# ledunit.net
KiCad netlist of a schematic drawn in EAGLE
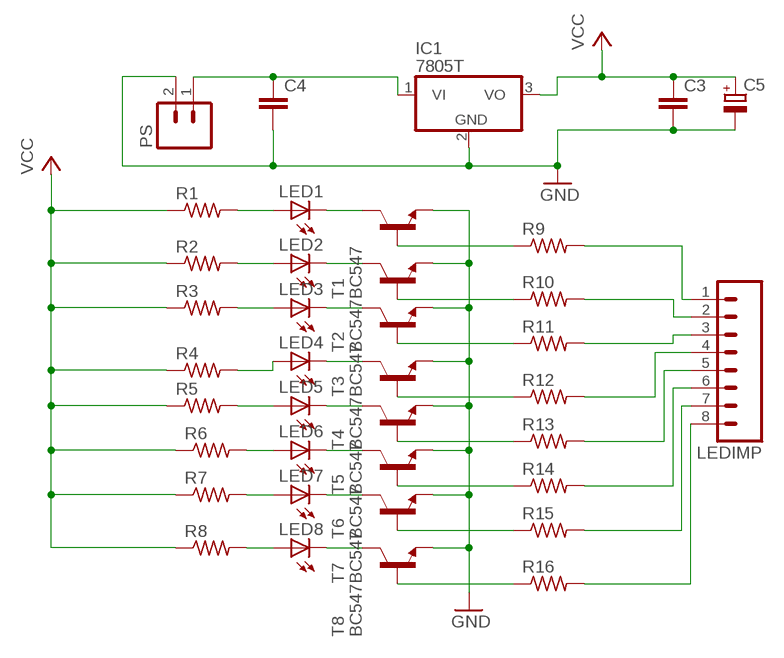
[diagram p0: schematic, sheet 1]

(export (version "E")
  (design (tool "Eeschema 10.0.6"))
  (components
    (comp (ref "C3")
      (value "C-EU025-024X044")
      (footprint "eagle-import:C025-024X044")
      (libsource (lib "eagle-import") (part "C-EU025-024X044"))
    )
    (comp (ref "C4")
      (value "C-EU025-024X044")
      (footprint "eagle-import:C025-024X044")
      (libsource (lib "eagle-import") (part "C-EU025-024X044"))
    )
    (comp (ref "C5")
      (value "CPOL-EUE2,5-6E")
      (footprint "eagle-import:E2,5-6E")
      (libsource (lib "eagle-import") (part "CPOL-EUE2,5-6E"))
    )
    (comp (ref "IC1")
      (value "7805T")
      (footprint "eagle-import:TO220H")
      (libsource (lib "eagle-import") (part "78T05"))
    )
    (comp (ref "LED1")
      (value "LED5MM")
      (footprint "eagle-import:LED5MM")
      (libsource (lib "eagle-import") (part "LED5MM"))
    )
    (comp (ref "LED2")
      (value "LED5MM")
      (footprint "eagle-import:LED5MM")
      (libsource (lib "eagle-import") (part "LED5MM"))
    )
    (comp (ref "LED3")
      (value "LED5MM")
      (footprint "eagle-import:LED5MM")
      (libsource (lib "eagle-import") (part "LED5MM"))
    )
    (comp (ref "LED4")
      (value "LED5MM")
      (footprint "eagle-import:LED5MM")
      (libsource (lib "eagle-import") (part "LED5MM"))
    )
    (comp (ref "LED5")
      (value "LED5MM")
      (footprint "eagle-import:LED5MM")
      (libsource (lib "eagle-import") (part "LED5MM"))
    )
    (comp (ref "LED6")
      (value "LED5MM")
      (footprint "eagle-import:LED5MM")
      (libsource (lib "eagle-import") (part "LED5MM"))
    )
    (comp (ref "LED7")
      (value "LED5MM")
      (footprint "eagle-import:LED5MM")
      (libsource (lib "eagle-import") (part "LED5MM"))
    )
    (comp (ref "LED8")
      (value "LED5MM")
      (footprint "eagle-import:LED5MM")
      (libsource (lib "eagle-import") (part "LED5MM"))
    )
    (comp (ref "LEDIMP")
      (value "M08")
      (footprint "eagle-import:08P")
      (libsource (lib "eagle-import") (part "M08"))
    )
    (comp (ref "PS")
      (value "M02")
      (footprint "eagle-import:02P")
      (libsource (lib "eagle-import") (part "M02"))
    )
    (comp (ref "R1")
      (value "R-US_0204/7")
      (footprint "eagle-import:0204_7")
      (libsource (lib "eagle-import") (part "R-US_0204/7"))
    )
    (comp (ref "R2")
      (value "R-US_0204/7")
      (footprint "eagle-import:0204_7")
      (libsource (lib "eagle-import") (part "R-US_0204/7"))
    )
    (comp (ref "R3")
      (value "R-US_0204/7")
      (footprint "eagle-import:0204_7")
      (libsource (lib "eagle-import") (part "R-US_0204/7"))
    )
    (comp (ref "R4")
      (value "R-US_0204/7")
      (footprint "eagle-import:0204_7")
      (libsource (lib "eagle-import") (part "R-US_0204/7"))
    )
    (comp (ref "R5")
      (value "R-US_0204/7")
      (footprint "eagle-import:0204_7")
      (libsource (lib "eagle-import") (part "R-US_0204/7"))
    )
    (comp (ref "R6")
      (value "R-US_0204/7")
      (footprint "eagle-import:0204_7")
      (libsource (lib "eagle-import") (part "R-US_0204/7"))
    )
    (comp (ref "R7")
      (value "R-US_0204/7")
      (footprint "eagle-import:0204_7")
      (libsource (lib "eagle-import") (part "R-US_0204/7"))
    )
    (comp (ref "R8")
      (value "R-US_0204/7")
      (footprint "eagle-import:0204_7")
      (libsource (lib "eagle-import") (part "R-US_0204/7"))
    )
    (comp (ref "R9")
      (value "R-US_0204/7")
      (footprint "eagle-import:0204_7")
      (libsource (lib "eagle-import") (part "R-US_0204/7"))
    )
    (comp (ref "R10")
      (value "R-US_0204/7")
      (footprint "eagle-import:0204_7")
      (libsource (lib "eagle-import") (part "R-US_0204/7"))
    )
    (comp (ref "R11")
      (value "R-US_0204/7")
      (footprint "eagle-import:0204_7")
      (libsource (lib "eagle-import") (part "R-US_0204/7"))
    )
    (comp (ref "R12")
      (value "R-US_0204/7")
      (footprint "eagle-import:0204_7")
      (libsource (lib "eagle-import") (part "R-US_0204/7"))
    )
    (comp (ref "R13")
      (value "R-US_0204/7")
      (footprint "eagle-import:0204_7")
      (libsource (lib "eagle-import") (part "R-US_0204/7"))
    )
    (comp (ref "R14")
      (value "R-US_0204/7")
      (footprint "eagle-import:0204_7")
      (libsource (lib "eagle-import") (part "R-US_0204/7"))
    )
    (comp (ref "R15")
      (value "R-US_0204/7")
      (footprint "eagle-import:0204_7")
      (libsource (lib "eagle-import") (part "R-US_0204/7"))
    )
    (comp (ref "R16")
      (value "R-US_0204/7")
      (footprint "eagle-import:0204_7")
      (libsource (lib "eagle-import") (part "R-US_0204/7"))
    )
    (comp (ref "T1")
      (value "BC547")
      (footprint "eagle-import:TO92")
      (libsource (lib "eagle-import") (part "BC547"))
    )
    (comp (ref "T2")
      (value "BC547")
      (footprint "eagle-import:TO92")
      (libsource (lib "eagle-import") (part "BC547"))
    )
    (comp (ref "T3")
      (value "BC547")
      (footprint "eagle-import:TO92")
      (libsource (lib "eagle-import") (part "BC547"))
    )
    (comp (ref "T4")
      (value "BC547")
      (footprint "eagle-import:TO92")
      (libsource (lib "eagle-import") (part "BC547"))
    )
    (comp (ref "T5")
      (value "BC547")
      (footprint "eagle-import:TO92")
      (libsource (lib "eagle-import") (part "BC547"))
    )
    (comp (ref "T6")
      (value "BC547")
      (footprint "eagle-import:TO92")
      (libsource (lib "eagle-import") (part "BC547"))
    )
    (comp (ref "T7")
      (value "BC547")
      (footprint "eagle-import:TO92")
      (libsource (lib "eagle-import") (part "BC547"))
    )
    (comp (ref "T8")
      (value "BC547")
      (footprint "eagle-import:TO92")
      (libsource (lib "eagle-import") (part "BC547"))
    )
  )
  (nets
    (net (code "1") (name "GND") (class "Default")
      (node (ref "C3") (pin "2") (pinfunction "2_2") (pintype "passive"))
      (node (ref "C4") (pin "2") (pinfunction "2_2") (pintype "passive"))
      (node (ref "C5") (pin "-") (pinfunction "-_-") (pintype "passive"))
      (node (ref "IC1") (pin "2") (pinfunction "GND_2") (pintype "passive"))
      (node (ref "PS") (pin "2") (pinfunction "2_2") (pintype "passive"))
      (node (ref "T1") (pin "1") (pinfunction "E_1") (pintype "passive"))
      (node (ref "T2") (pin "1") (pinfunction "E_1") (pintype "passive"))
      (node (ref "T3") (pin "1") (pinfunction "E_1") (pintype "passive"))
      (node (ref "T4") (pin "1") (pinfunction "E_1") (pintype "passive"))
      (node (ref "T5") (pin "1") (pinfunction "E_1") (pintype "passive"))
      (node (ref "T6") (pin "1") (pinfunction "E_1") (pintype "passive"))
      (node (ref "T7") (pin "1") (pinfunction "E_1") (pintype "passive"))
      (node (ref "T8") (pin "1") (pinfunction "E_1") (pintype "passive"))
    )
    (net (code "2") (name "Net-(IC1-VI)") (class "Default")
      (node (ref "C4") (pin "1") (pinfunction "1_1") (pintype "passive"))
      (node (ref "IC1") (pin "1") (pinfunction "VI_1") (pintype "input"))
      (node (ref "PS") (pin "1") (pinfunction "1_1") (pintype "passive"))
    )
    (net (code "3") (name "Net-(LED1-C)") (class "Default")
      (node (ref "LED1") (pin "K") (pinfunction "C_K") (pintype "passive"))
      (node (ref "T1") (pin "3") (pinfunction "C_3") (pintype "passive"))
    )
    (net (code "4") (name "Net-(LED1-PadA)") (class "Default")
      (node (ref "LED1") (pin "A") (pinfunction "A_A") (pintype "passive"))
      (node (ref "R1") (pin "2") (pinfunction "2_2") (pintype "passive"))
    )
    (net (code "5") (name "Net-(LED2-C)") (class "Default")
      (node (ref "LED2") (pin "K") (pinfunction "C_K") (pintype "passive"))
      (node (ref "T2") (pin "3") (pinfunction "C_3") (pintype "passive"))
    )
    (net (code "6") (name "Net-(LED2-PadA)") (class "Default")
      (node (ref "LED2") (pin "A") (pinfunction "A_A") (pintype "passive"))
      (node (ref "R2") (pin "2") (pinfunction "2_2") (pintype "passive"))
    )
    (net (code "7") (name "Net-(LED3-C)") (class "Default")
      (node (ref "LED3") (pin "K") (pinfunction "C_K") (pintype "passive"))
      (node (ref "T3") (pin "3") (pinfunction "C_3") (pintype "passive"))
    )
    (net (code "8") (name "Net-(LED3-PadA)") (class "Default")
      (node (ref "LED3") (pin "A") (pinfunction "A_A") (pintype "passive"))
      (node (ref "R3") (pin "2") (pinfunction "2_2") (pintype "passive"))
    )
    (net (code "9") (name "Net-(LED4-C)") (class "Default")
      (node (ref "LED4") (pin "K") (pinfunction "C_K") (pintype "passive"))
      (node (ref "T4") (pin "3") (pinfunction "C_3") (pintype "passive"))
    )
    (net (code "10") (name "Net-(LED4-PadA)") (class "Default")
      (node (ref "LED4") (pin "A") (pinfunction "A_A") (pintype "passive"))
      (node (ref "R4") (pin "2") (pinfunction "2_2") (pintype "passive"))
    )
    (net (code "11") (name "Net-(LED5-C)") (class "Default")
      (node (ref "LED5") (pin "K") (pinfunction "C_K") (pintype "passive"))
      (node (ref "T5") (pin "3") (pinfunction "C_3") (pintype "passive"))
    )
    (net (code "12") (name "Net-(LED5-PadA)") (class "Default")
      (node (ref "LED5") (pin "A") (pinfunction "A_A") (pintype "passive"))
      (node (ref "R5") (pin "2") (pinfunction "2_2") (pintype "passive"))
    )
    (net (code "13") (name "Net-(LED6-C)") (class "Default")
      (node (ref "LED6") (pin "K") (pinfunction "C_K") (pintype "passive"))
      (node (ref "T6") (pin "3") (pinfunction "C_3") (pintype "passive"))
    )
    (net (code "14") (name "Net-(LED6-PadA)") (class "Default")
      (node (ref "LED6") (pin "A") (pinfunction "A_A") (pintype "passive"))
      (node (ref "R6") (pin "2") (pinfunction "2_2") (pintype "passive"))
    )
    (net (code "15") (name "Net-(LED7-C)") (class "Default")
      (node (ref "LED7") (pin "K") (pinfunction "C_K") (pintype "passive"))
      (node (ref "T7") (pin "3") (pinfunction "C_3") (pintype "passive"))
    )
    (net (code "16") (name "Net-(LED7-PadA)") (class "Default")
      (node (ref "LED7") (pin "A") (pinfunction "A_A") (pintype "passive"))
      (node (ref "R7") (pin "2") (pinfunction "2_2") (pintype "passive"))
    )
    (net (code "17") (name "Net-(LED8-C)") (class "Default")
      (node (ref "LED8") (pin "K") (pinfunction "C_K") (pintype "passive"))
      (node (ref "T8") (pin "3") (pinfunction "C_3") (pintype "passive"))
    )
    (net (code "18") (name "Net-(LED8-PadA)") (class "Default")
      (node (ref "LED8") (pin "A") (pinfunction "A_A") (pintype "passive"))
      (node (ref "R8") (pin "2") (pinfunction "2_2") (pintype "passive"))
    )
    (net (code "19") (name "Net-(LEDIMP-Pad1)") (class "Default")
      (node (ref "LEDIMP") (pin "1") (pinfunction "1_1") (pintype "passive"))
      (node (ref "R9") (pin "2") (pinfunction "2_2") (pintype "passive"))
    )
    (net (code "20") (name "Net-(LEDIMP-Pad2)") (class "Default")
      (node (ref "LEDIMP") (pin "2") (pinfunction "2_2") (pintype "passive"))
      (node (ref "R10") (pin "2") (pinfunction "2_2") (pintype "passive"))
    )
    (net (code "21") (name "Net-(LEDIMP-Pad3)") (class "Default")
      (node (ref "LEDIMP") (pin "3") (pinfunction "3_3") (pintype "passive"))
      (node (ref "R11") (pin "2") (pinfunction "2_2") (pintype "passive"))
    )
    (net (code "22") (name "Net-(LEDIMP-Pad4)") (class "Default")
      (node (ref "LEDIMP") (pin "4") (pinfunction "4_4") (pintype "passive"))
      (node (ref "R12") (pin "2") (pinfunction "2_2") (pintype "passive"))
    )
    (net (code "23") (name "Net-(LEDIMP-Pad5)") (class "Default")
      (node (ref "LEDIMP") (pin "5") (pinfunction "5_5") (pintype "passive"))
      (node (ref "R13") (pin "2") (pinfunction "2_2") (pintype "passive"))
    )
    (net (code "24") (name "Net-(LEDIMP-Pad6)") (class "Default")
      (node (ref "LEDIMP") (pin "6") (pinfunction "6_6") (pintype "passive"))
      (node (ref "R14") (pin "2") (pinfunction "2_2") (pintype "passive"))
    )
    (net (code "25") (name "Net-(LEDIMP-Pad7)") (class "Default")
      (node (ref "LEDIMP") (pin "7") (pinfunction "7_7") (pintype "passive"))
      (node (ref "R15") (pin "2") (pinfunction "2_2") (pintype "passive"))
    )
    (net (code "26") (name "Net-(LEDIMP-Pad8)") (class "Default")
      (node (ref "LEDIMP") (pin "8") (pinfunction "8_8") (pintype "passive"))
      (node (ref "R16") (pin "2") (pinfunction "2_2") (pintype "passive"))
    )
    (net (code "27") (name "Net-(T1-B)") (class "Default")
      (node (ref "R9") (pin "1") (pinfunction "1_1") (pintype "passive"))
      (node (ref "T1") (pin "2") (pinfunction "B_2") (pintype "passive"))
    )
    (net (code "28") (name "Net-(T2-B)") (class "Default")
      (node (ref "R10") (pin "1") (pinfunction "1_1") (pintype "passive"))
      (node (ref "T2") (pin "2") (pinfunction "B_2") (pintype "passive"))
    )
    (net (code "29") (name "Net-(T3-B)") (class "Default")
      (node (ref "R11") (pin "1") (pinfunction "1_1") (pintype "passive"))
      (node (ref "T3") (pin "2") (pinfunction "B_2") (pintype "passive"))
    )
    (net (code "30") (name "Net-(T4-B)") (class "Default")
      (node (ref "R12") (pin "1") (pinfunction "1_1") (pintype "passive"))
      (node (ref "T4") (pin "2") (pinfunction "B_2") (pintype "passive"))
    )
    (net (code "31") (name "Net-(T5-B)") (class "Default")
      (node (ref "R13") (pin "1") (pinfunction "1_1") (pintype "passive"))
      (node (ref "T5") (pin "2") (pinfunction "B_2") (pintype "passive"))
    )
    (net (code "32") (name "Net-(T6-B)") (class "Default")
      (node (ref "R14") (pin "1") (pinfunction "1_1") (pintype "passive"))
      (node (ref "T6") (pin "2") (pinfunction "B_2") (pintype "passive"))
    )
    (net (code "33") (name "Net-(T7-B)") (class "Default")
      (node (ref "R15") (pin "1") (pinfunction "1_1") (pintype "passive"))
      (node (ref "T7") (pin "2") (pinfunction "B_2") (pintype "passive"))
    )
    (net (code "34") (name "Net-(T8-B)") (class "Default")
      (node (ref "R16") (pin "1") (pinfunction "1_1") (pintype "passive"))
      (node (ref "T8") (pin "2") (pinfunction "B_2") (pintype "passive"))
    )
    (net (code "35") (name "VCC") (class "Default")
      (node (ref "C3") (pin "1") (pinfunction "1_1") (pintype "passive"))
      (node (ref "C5") (pin "+") (pinfunction "+_+") (pintype "passive"))
      (node (ref "IC1") (pin "3") (pinfunction "VO_3") (pintype "passive"))
      (node (ref "R1") (pin "1") (pinfunction "1_1") (pintype "passive"))
      (node (ref "R2") (pin "1") (pinfunction "1_1") (pintype "passive"))
      (node (ref "R3") (pin "1") (pinfunction "1_1") (pintype "passive"))
      (node (ref "R4") (pin "1") (pinfunction "1_1") (pintype "passive"))
      (node (ref "R5") (pin "1") (pinfunction "1_1") (pintype "passive"))
      (node (ref "R6") (pin "1") (pinfunction "1_1") (pintype "passive"))
      (node (ref "R7") (pin "1") (pinfunction "1_1") (pintype "passive"))
      (node (ref "R8") (pin "1") (pinfunction "1_1") (pintype "passive"))
    )
  )
)
